# AS6212_breakout.net
KiCad netlist of a schematic drawn in EAGLE
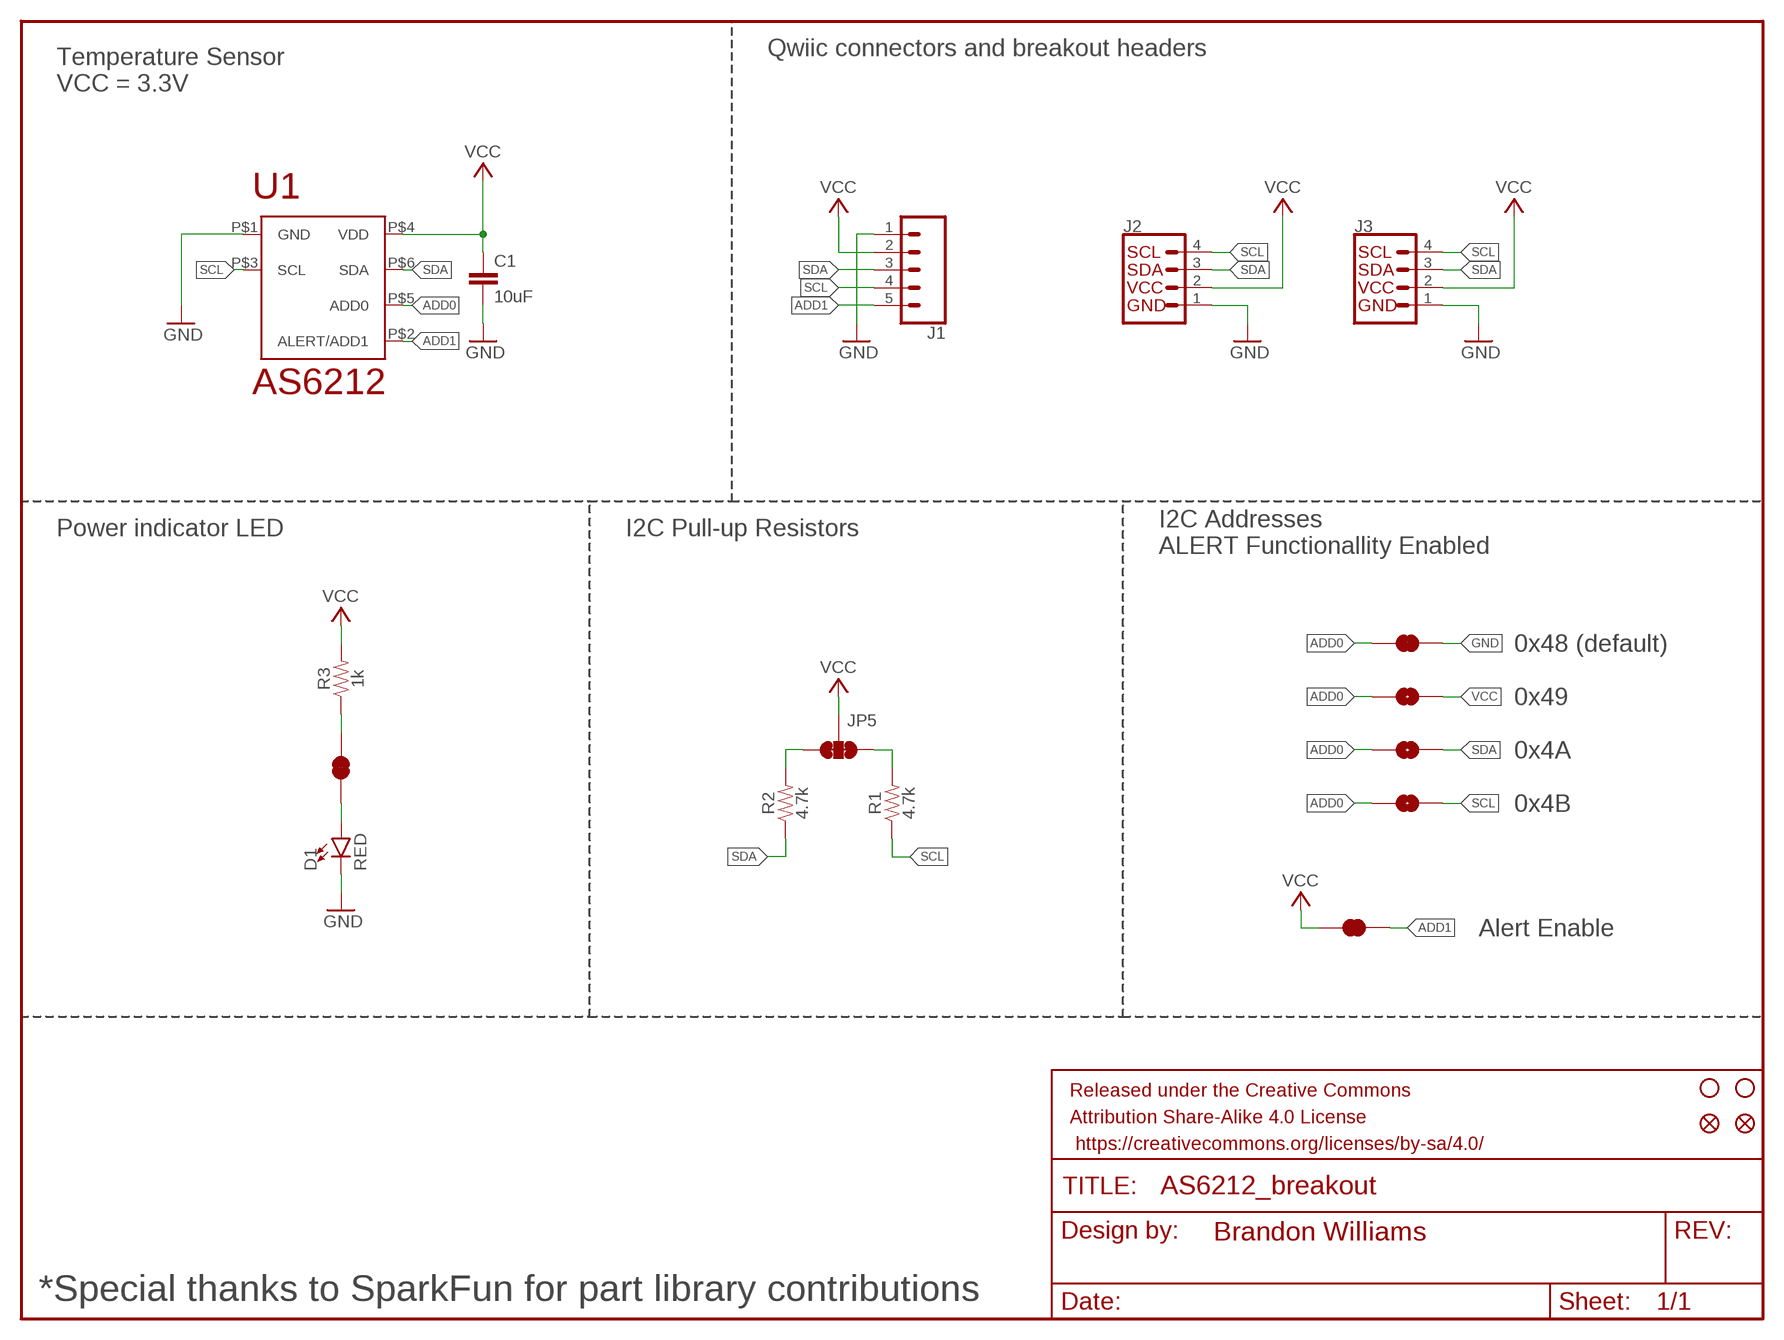
[diagram p0: schematic, sheet 1]

(export (version "E")
  (design (tool "Eeschema 10.0.6"))
  (components
    (comp (ref "C1")
      (value "10uF")
      (footprint "eagle-import:0805")
      (libsource (lib "eagle-import") (part "10UF-0805-25V-10%"))
    )
    (comp (ref "D1")
      (value "RED")
      (footprint "eagle-import:LED-0603")
      (libsource (lib "eagle-import") (part "LED-RED0603"))
    )
    (comp (ref "FD1")
      (value "FIDUCIAL0.2MM")
      (footprint "eagle-import:FIDUCIAL-0.2MM")
      (libsource (lib "eagle-import") (part "FIDUCIAL0.2MM"))
    )
    (comp (ref "FD2")
      (value "FIDUCIAL0.2MM")
      (footprint "eagle-import:FIDUCIAL-0.2MM")
      (libsource (lib "eagle-import") (part "FIDUCIAL0.2MM"))
    )
    (comp (ref "FRAME1")
      (value "FRAME-LETTERNO_PACKAGE")
      (footprint "eagle-import:DUMMY")
      (fields (field (name "DESIGNER") "Brandon Williams") (field (name "DESIGNER_1") "Brandon Williams"))
      (libsource (lib "eagle-import") (part "FRAME-LETTERNO_PACKAGE"))
    )
    (comp (ref "H1")
      (value "STAND-OFF")
      (footprint "eagle-import:STAND-OFF")
      (libsource (lib "eagle-import") (part "STAND-OFF"))
    )
    (comp (ref "H2")
      (value "STAND-OFF")
      (footprint "eagle-import:STAND-OFF")
      (libsource (lib "eagle-import") (part "STAND-OFF"))
    )
    (comp (ref "J1")
      (value "CONN_05")
      (footprint "eagle-import:1X05")
      (libsource (lib "eagle-import") (part "CONN_05"))
    )
    (comp (ref "J2")
      (value "QWIIC_RIGHT_ANGLE")
      (footprint "eagle-import:JST04_1MM_RA")
      (libsource (lib "eagle-import") (part "QWIIC_CONNECTORJS-1MM"))
    )
    (comp (ref "J3")
      (value "QWIIC_RIGHT_ANGLE")
      (footprint "eagle-import:JST04_1MM_RA")
      (libsource (lib "eagle-import") (part "QWIIC_CONNECTORJS-1MM"))
    )
    (comp (ref "JP1")
      (value "JUMPER-SMT_2_NO_SILK")
      (footprint "eagle-import:SMT-JUMPER_2_NO_SILK")
      (libsource (lib "eagle-import") (part "JUMPER-SMT_2_NO_SILK"))
    )
    (comp (ref "JP2")
      (value "JUMPER-SMT_2_NO_SILK")
      (footprint "eagle-import:SMT-JUMPER_2_NO_SILK")
      (libsource (lib "eagle-import") (part "JUMPER-SMT_2_NO_SILK"))
    )
    (comp (ref "JP3")
      (value "JUMPER-SMT_2_NO_SILK")
      (footprint "eagle-import:SMT-JUMPER_2_NO_SILK")
      (libsource (lib "eagle-import") (part "JUMPER-SMT_2_NO_SILK"))
    )
    (comp (ref "JP4")
      (value "JUMPER-SMT_2_NC_TRACE_SILK")
      (footprint "eagle-import:SMT-JUMPER_2_NC_TRACE_SILK")
      (libsource (lib "eagle-import") (part "JUMPER-SMT_2_NC_TRACE_SILK"))
    )
    (comp (ref "JP5")
      (value "JUMPER-SMT_3_2-NC_TRACE_SILK")
      (footprint "eagle-import:SMT-JUMPER_3_2-NC_TRACE_SILK")
      (libsource (lib "eagle-import") (part "JUMPER-SMT_3_2-NC_TRACE_SILK"))
    )
    (comp (ref "JP6")
      (value "JUMPER-SMT_2_NC_TRACE_SILK")
      (footprint "eagle-import:SMT-JUMPER_2_NC_TRACE_SILK")
      (libsource (lib "eagle-import") (part "JUMPER-SMT_2_NC_TRACE_SILK"))
    )
    (comp (ref "JP7")
      (value "JUMPER-SMT_2_NC_TRACE_SILK")
      (footprint "eagle-import:SMT-JUMPER_2_NC_TRACE_SILK")
      (libsource (lib "eagle-import") (part "JUMPER-SMT_2_NC_TRACE_SILK"))
    )
    (comp (ref "R1")
      (value "4.7k")
      (footprint "eagle-import:0603")
      (libsource (lib "eagle-import") (part "4.7KOHM-0603-1/10W-1%"))
    )
    (comp (ref "R2")
      (value "4.7k")
      (footprint "eagle-import:0603")
      (libsource (lib "eagle-import") (part "4.7KOHM-0603-1/10W-1%"))
    )
    (comp (ref "R3")
      (value "1k")
      (footprint "eagle-import:0603")
      (libsource (lib "eagle-import") (part "1KOHM-0603-1/10W-1%"))
    )
    (comp (ref "U1")
      (value "AS6212")
      (footprint "eagle-import:AS6212")
      (libsource (lib "eagle-import") (part "AS6212"))
    )
  )
  (nets
    (net (code "1") (name "ADD0") (class "Default")
      (node (ref "JP1") (pin "1") (pinfunction "1_1") (pintype "passive"))
      (node (ref "JP2") (pin "1") (pinfunction "1_1") (pintype "passive"))
      (node (ref "JP3") (pin "1") (pinfunction "1_1") (pintype "passive"))
      (node (ref "JP4") (pin "1") (pinfunction "1_1") (pintype "passive"))
      (node (ref "U1") (pin "P$5") (pinfunction "ADD0_P$5") (pintype "bidirectional"))
    )
    (net (code "2") (name "ADD1") (class "Default")
      (node (ref "J1") (pin "5") (pinfunction "5_5") (pintype "passive"))
      (node (ref "JP6") (pin "2") (pinfunction "2_2") (pintype "passive"))
      (node (ref "U1") (pin "P$2") (pinfunction "ALERT/ADD1_P$2") (pintype "bidirectional"))
    )
    (net (code "3") (name "GND") (class "Default")
      (node (ref "C1") (pin "2") (pinfunction "2_2") (pintype "passive"))
      (node (ref "D1") (pin "C") (pinfunction "C_C") (pintype "passive"))
      (node (ref "J1") (pin "1") (pinfunction "1_1") (pintype "passive"))
      (node (ref "J2") (pin "1") (pinfunction "1_1") (pintype "power_in"))
      (node (ref "J3") (pin "1") (pinfunction "1_1") (pintype "power_in"))
      (node (ref "JP4") (pin "2") (pinfunction "2_2") (pintype "passive"))
      (node (ref "U1") (pin "P$1") (pinfunction "GND_P$1") (pintype "power_in"))
    )
    (net (code "4") (name "Net-(D1-PadA)") (class "Default")
      (node (ref "D1") (pin "A") (pinfunction "A_A") (pintype "passive"))
      (node (ref "JP7") (pin "1") (pinfunction "1_1") (pintype "passive"))
    )
    (net (code "5") (name "Net-(JP5-Pad1)") (class "Default")
      (node (ref "JP5") (pin "1") (pinfunction "1_1") (pintype "passive"))
      (node (ref "R1") (pin "2") (pinfunction "2_2") (pintype "passive"))
    )
    (net (code "6") (name "Net-(JP5-Pad3)") (class "Default")
      (node (ref "JP5") (pin "3") (pinfunction "3_3") (pintype "passive"))
      (node (ref "R2") (pin "2") (pinfunction "2_2") (pintype "passive"))
    )
    (net (code "7") (name "Net-(JP7-Pad2)") (class "Default")
      (node (ref "JP7") (pin "2") (pinfunction "2_2") (pintype "passive"))
      (node (ref "R3") (pin "1") (pinfunction "1_1") (pintype "passive"))
    )
    (net (code "8") (name "SCL") (class "Default")
      (node (ref "J1") (pin "4") (pinfunction "4_4") (pintype "passive"))
      (node (ref "J2") (pin "4") (pinfunction "4_4") (pintype "passive"))
      (node (ref "J3") (pin "4") (pinfunction "4_4") (pintype "passive"))
      (node (ref "JP2") (pin "2") (pinfunction "2_2") (pintype "passive"))
      (node (ref "R1") (pin "1") (pinfunction "1_1") (pintype "passive"))
      (node (ref "U1") (pin "P$3") (pinfunction "SCL_P$3") (pintype "bidirectional"))
    )
    (net (code "9") (name "SDA") (class "Default")
      (node (ref "J1") (pin "3") (pinfunction "3_3") (pintype "passive"))
      (node (ref "J2") (pin "3") (pinfunction "3_3") (pintype "passive"))
      (node (ref "J3") (pin "3") (pinfunction "3_3") (pintype "passive"))
      (node (ref "JP1") (pin "2") (pinfunction "2_2") (pintype "passive"))
      (node (ref "R2") (pin "1") (pinfunction "1_1") (pintype "passive"))
      (node (ref "U1") (pin "P$6") (pinfunction "SDA_P$6") (pintype "bidirectional"))
    )
    (net (code "10") (name "VCC") (class "Default")
      (node (ref "C1") (pin "1") (pinfunction "1_1") (pintype "passive"))
      (node (ref "J1") (pin "2") (pinfunction "2_2") (pintype "passive"))
      (node (ref "J2") (pin "2") (pinfunction "2_2") (pintype "power_in"))
      (node (ref "J3") (pin "2") (pinfunction "2_2") (pintype "power_in"))
      (node (ref "JP3") (pin "2") (pinfunction "2_2") (pintype "passive"))
      (node (ref "JP5") (pin "2") (pinfunction "2_2") (pintype "passive"))
      (node (ref "JP6") (pin "1") (pinfunction "1_1") (pintype "passive"))
      (node (ref "R3") (pin "2") (pinfunction "2_2") (pintype "passive"))
      (node (ref "U1") (pin "P$4") (pinfunction "VDD_P$4") (pintype "power_in"))
    )
  )
)
